# USBHSULPI.net
KiCad netlist of a schematic drawn in Altium Designer
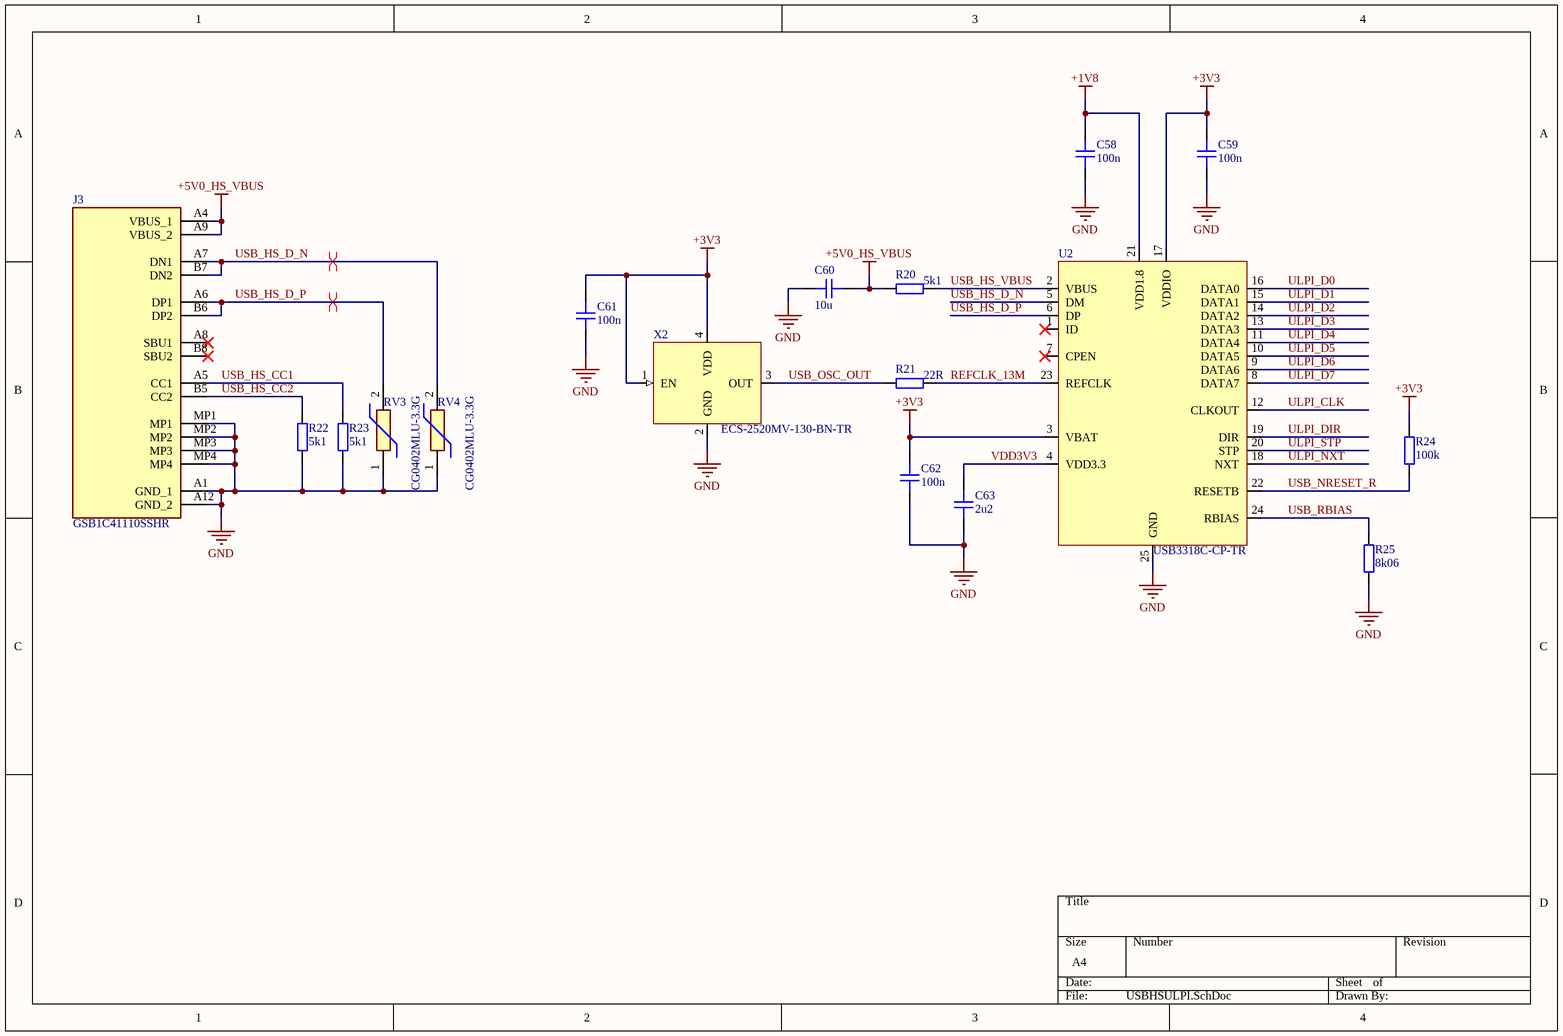
[diagram p0: USBHSULPI.SchDoc]

(export (version "E")
  (design (tool "Eeschema 10.0.6"))
  (components
    (comp (ref "C58")
      (value "100n")
      (footprint "CAP_0402")
      (description "Capacitor SMD 0402")
      (libsource (lib "Schematic-Lib-PhilsLab") (part "CAP_0402"))
    )
    (comp (ref "C59")
      (value "100n")
      (footprint "CAP_0402")
      (description "Capacitor SMD 0402")
      (libsource (lib "Schematic-Lib-PhilsLab") (part "CAP_0402"))
    )
    (comp (ref "C60")
      (value "10u")
      (footprint "CAP_0603")
      (description "Capacitor SMD 0603")
      (libsource (lib "Schematic-Lib-PhilsLab") (part "CAP_0603"))
    )
    (comp (ref "C61")
      (value "100n")
      (footprint "CAP_0402")
      (description "Capacitor SMD 0402")
      (libsource (lib "Schematic-Lib-PhilsLab") (part "CAP_0402"))
    )
    (comp (ref "C62")
      (value "100n")
      (footprint "CAP_0402")
      (description "Capacitor SMD 0402")
      (libsource (lib "Schematic-Lib-PhilsLab") (part "CAP_0402"))
    )
    (comp (ref "C63")
      (value "2u2")
      (footprint "CAP_0402")
      (description "Capacitor SMD 0402")
      (libsource (lib "Schematic-Lib-PhilsLab") (part "CAP_0402"))
    )
    (comp (ref "J3")
      (value "GSB1C41110SSHR")
      (footprint "Footprint-Lib-PhilsLab:GSB1C41110SSHR")
      (description "Connector")
      (libsource (lib "Schematic-Lib-PhilsLab") (part "GSB1C41110SSHR"))
    )
    (comp (ref "R20")
      (value "5k1")
      (footprint "RES_0402")
      (description "Resistor SMD 0402")
      (libsource (lib "Schematic-Lib-PhilsLab") (part "RES_0402"))
    )
    (comp (ref "R21")
      (value "22R")
      (footprint "RES_0402")
      (description "Resistor SMD 0402")
      (libsource (lib "Schematic-Lib-PhilsLab") (part "RES_0402"))
    )
    (comp (ref "R22")
      (value "5k1")
      (footprint "RES_0402")
      (description "Resistor SMD 0402")
      (libsource (lib "Schematic-Lib-PhilsLab") (part "RES_0402"))
    )
    (comp (ref "R23")
      (value "5k1")
      (footprint "RES_0402")
      (description "Resistor SMD 0402")
      (libsource (lib "Schematic-Lib-PhilsLab") (part "RES_0402"))
    )
    (comp (ref "R24")
      (value "100k")
      (footprint "RES_0402")
      (description "Resistor SMD 0402")
      (libsource (lib "Schematic-Lib-PhilsLab") (part "RES_0402"))
    )
    (comp (ref "R25")
      (value "8k06")
      (footprint "RES_0402")
      (description "Resistor SMD 0402")
      (libsource (lib "Schematic-Lib-PhilsLab") (part "RES_0402"))
    )
    (comp (ref "RV3")
      (value "CG0402MLU-3.3G")
      (footprint "Footprint-Lib-PhilsLab:VARC1005X41N")
      (description "ESD Diode")
      (fields (field (name "MOUSER PART NUMBER") "652-CG0402MLU-3.3G"))
      (libsource (lib "Schematic-Lib-PhilsLab") (part "CG0402MLU-3.3G"))
    )
    (comp (ref "RV4")
      (value "CG0402MLU-3.3G")
      (footprint "Footprint-Lib-PhilsLab:VARC1005X41N")
      (description "ESD Diode")
      (fields (field (name "MOUSER PART NUMBER") "652-CG0402MLU-3.3G"))
      (libsource (lib "Schematic-Lib-PhilsLab") (part "CG0402MLU-3.3G"))
    )
    (comp (ref "U2")
      (value "USB3318C-CP-TR")
      (footprint "QFN50P400X400X100-25N-D")
      (description "USB Interface IC High Speed USB 1.8V ULPI")
      (fields (field (name "MANUFACTURER") "Microchip"))
      (libsource (lib "Schematic-Lib-PhilsLab") (part "USB3318C-CP-TR"))
    )
    (comp (ref "X2")
      (value "ECS-2520MV-130-BN-TR")
      (footprint "XTAL_2520")
      (fields (field (name "MANUFACTURER") "ECS"))
      (libsource (lib "Schematic-Lib-PhilsLab") (part "ECS-2520MV-130-BN-TR"))
    )
  )
  (nets
    (net (code "1") (name "+1V8") (class "Default")
      (node (ref "C58") (pin "2") (pinfunction "2_2") (pintype "passive"))
      (node (ref "U2") (pin "21") (pinfunction "VDD1.8_21") (pintype "passive"))
    )
    (net (code "2") (name "+3V3") (class "Default")
      (node (ref "C59") (pin "2") (pinfunction "2_2") (pintype "passive"))
      (node (ref "C61") (pin "2") (pinfunction "2_2") (pintype "passive"))
      (node (ref "C62") (pin "2") (pinfunction "2_2") (pintype "passive"))
      (node (ref "R24") (pin "1") (pinfunction "1_1") (pintype "passive"))
      (node (ref "U2") (pin "17") (pinfunction "VDDIO_17") (pintype "passive"))
      (node (ref "U2") (pin "3") (pinfunction "VBAT_3") (pintype "passive"))
      (node (ref "X2") (pin "1") (pinfunction "EN_1") (pintype "input"))
      (node (ref "X2") (pin "4") (pinfunction "VDD_4") (pintype "power_in"))
    )
    (net (code "3") (name "+5V0_HS_VBUS") (class "Default")
      (node (ref "C60") (pin "1") (pinfunction "1_1") (pintype "passive"))
      (node (ref "J3") (pin "A4") (pinfunction "VBUS_1_A4") (pintype "passive"))
      (node (ref "J3") (pin "A9") (pinfunction "VBUS_2_A9") (pintype "passive"))
      (node (ref "R20") (pin "2") (pinfunction "2_2") (pintype "passive"))
    )
    (net (code "4") (name "/REFCLK_13M") (class "Default")
      (node (ref "R21") (pin "1") (pinfunction "1_1") (pintype "passive"))
      (node (ref "U2") (pin "23") (pinfunction "REFCLK_23") (pintype "passive"))
    )
    (net (code "5") (name "/ULPI_CLK") (class "Default")
      (node (ref "U2") (pin "12") (pinfunction "CLKOUT_12") (pintype "passive"))
    )
    (net (code "6") (name "/ULPI_D0") (class "Default")
      (node (ref "U2") (pin "16") (pinfunction "DATA0_16") (pintype "passive"))
    )
    (net (code "7") (name "/ULPI_D1") (class "Default")
      (node (ref "U2") (pin "15") (pinfunction "DATA1_15") (pintype "passive"))
    )
    (net (code "8") (name "/ULPI_D2") (class "Default")
      (node (ref "U2") (pin "14") (pinfunction "DATA2_14") (pintype "passive"))
    )
    (net (code "9") (name "/ULPI_D3") (class "Default")
      (node (ref "U2") (pin "13") (pinfunction "DATA3_13") (pintype "passive"))
    )
    (net (code "10") (name "/ULPI_D4") (class "Default")
      (node (ref "U2") (pin "11") (pinfunction "DATA4_11") (pintype "passive"))
    )
    (net (code "11") (name "/ULPI_D5") (class "Default")
      (node (ref "U2") (pin "10") (pinfunction "DATA5_10") (pintype "passive"))
    )
    (net (code "12") (name "/ULPI_D6") (class "Default")
      (node (ref "U2") (pin "9") (pinfunction "DATA6_9") (pintype "passive"))
    )
    (net (code "13") (name "/ULPI_D7") (class "Default")
      (node (ref "U2") (pin "8") (pinfunction "DATA7_8") (pintype "passive"))
    )
    (net (code "14") (name "/ULPI_DIR") (class "Default")
      (node (ref "U2") (pin "19") (pinfunction "DIR_19") (pintype "passive"))
    )
    (net (code "15") (name "/ULPI_NXT") (class "Default")
      (node (ref "U2") (pin "18") (pinfunction "NXT_18") (pintype "passive"))
    )
    (net (code "16") (name "/ULPI_STP") (class "Default")
      (node (ref "U2") (pin "20") (pinfunction "STP_20") (pintype "passive"))
    )
    (net (code "17") (name "/USB_HS_CC1") (class "Default")
      (node (ref "J3") (pin "A5") (pinfunction "CC1_A5") (pintype "passive"))
      (node (ref "R23") (pin "1") (pinfunction "1_1") (pintype "passive"))
    )
    (net (code "18") (name "/USB_HS_CC2") (class "Default")
      (node (ref "J3") (pin "B5") (pinfunction "CC2_B5") (pintype "passive"))
      (node (ref "R22") (pin "1") (pinfunction "1_1") (pintype "passive"))
    )
    (net (code "19") (name "/USB_HS_D_N") (class "Default")
      (node (ref "J3") (pin "A7") (pinfunction "DN1_A7") (pintype "passive"))
      (node (ref "J3") (pin "B7") (pinfunction "DN2_B7") (pintype "passive"))
      (node (ref "RV4") (pin "2") (pinfunction "2_2") (pintype "passive"))
      (node (ref "U2") (pin "5") (pinfunction "DM_5") (pintype "passive"))
    )
    (net (code "20") (name "/USB_HS_D_P") (class "Default")
      (node (ref "J3") (pin "A6") (pinfunction "DP1_A6") (pintype "passive"))
      (node (ref "J3") (pin "B6") (pinfunction "DP2_B6") (pintype "passive"))
      (node (ref "RV3") (pin "2") (pinfunction "2_2") (pintype "passive"))
      (node (ref "U2") (pin "6") (pinfunction "DP_6") (pintype "passive"))
    )
    (net (code "21") (name "/USB_HS_VBUS") (class "Default")
      (node (ref "R20") (pin "1") (pinfunction "1_1") (pintype "passive"))
      (node (ref "U2") (pin "2") (pinfunction "VBUS_2") (pintype "passive"))
    )
    (net (code "22") (name "/USB_NRESET_R") (class "Default")
      (node (ref "R24") (pin "2") (pinfunction "2_2") (pintype "passive"))
      (node (ref "U2") (pin "22") (pinfunction "RESETB_22") (pintype "passive"))
    )
    (net (code "23") (name "/USB_OSC_OUT") (class "Default")
      (node (ref "R21") (pin "2") (pinfunction "2_2") (pintype "passive"))
      (node (ref "X2") (pin "3") (pinfunction "OUT_3") (pintype "passive"))
    )
    (net (code "24") (name "/USB_RBIAS") (class "Default")
      (node (ref "R25") (pin "2") (pinfunction "2_2") (pintype "passive"))
      (node (ref "U2") (pin "24") (pinfunction "RBIAS_24") (pintype "passive"))
    )
    (net (code "25") (name "/VDD3V3") (class "Default")
      (node (ref "C63") (pin "2") (pinfunction "2_2") (pintype "passive"))
      (node (ref "U2") (pin "4") (pinfunction "VDD3.3_4") (pintype "passive"))
    )
    (net (code "26") (name "GND") (class "Default")
      (node (ref "C58") (pin "1") (pinfunction "1_1") (pintype "passive"))
      (node (ref "C59") (pin "1") (pinfunction "1_1") (pintype "passive"))
      (node (ref "C60") (pin "2") (pinfunction "2_2") (pintype "passive"))
      (node (ref "C61") (pin "1") (pinfunction "1_1") (pintype "passive"))
      (node (ref "C62") (pin "1") (pinfunction "1_1") (pintype "passive"))
      (node (ref "C63") (pin "1") (pinfunction "1_1") (pintype "passive"))
      (node (ref "J3") (pin "A1") (pinfunction "GND_1_A1") (pintype "passive"))
      (node (ref "J3") (pin "A12") (pinfunction "GND_2_A12") (pintype "passive"))
      (node (ref "J3") (pin "MP1") (pinfunction "MP1_MP1") (pintype "passive"))
      (node (ref "J3") (pin "MP2") (pinfunction "MP2_MP2") (pintype "passive"))
      (node (ref "J3") (pin "MP3") (pinfunction "MP3_MP3") (pintype "passive"))
      (node (ref "J3") (pin "MP4") (pinfunction "MP4_MP4") (pintype "passive"))
      (node (ref "R22") (pin "2") (pinfunction "2_2") (pintype "passive"))
      (node (ref "R23") (pin "2") (pinfunction "2_2") (pintype "passive"))
      (node (ref "R25") (pin "1") (pinfunction "1_1") (pintype "passive"))
      (node (ref "RV3") (pin "1") (pinfunction "1_1") (pintype "passive"))
      (node (ref "RV4") (pin "1") (pinfunction "1_1") (pintype "passive"))
      (node (ref "U2") (pin "25") (pinfunction "GND_25") (pintype "passive"))
      (node (ref "X2") (pin "2") (pinfunction "GND_2") (pintype "power_in"))
    )
    (net (code "27") (name "unconnected-(J3-SBU1-PadA8)") (class "Default")
      (node (ref "J3") (pin "A8") (pinfunction "SBU1_A8") (pintype "passive+no_connect"))
    )
    (net (code "28") (name "unconnected-(J3-SBU2-PadB8)") (class "Default")
      (node (ref "J3") (pin "B8") (pinfunction "SBU2_B8") (pintype "passive+no_connect"))
    )
    (net (code "29") (name "unconnected-(U2-CPEN-Pad7)") (class "Default")
      (node (ref "U2") (pin "7") (pinfunction "CPEN_7") (pintype "passive+no_connect"))
    )
    (net (code "30") (name "unconnected-(U2-ID-Pad1)") (class "Default")
      (node (ref "U2") (pin "1") (pinfunction "ID_1") (pintype "passive+no_connect"))
    )
  )
)
